# sw4.net
KiCad netlist of a schematic drawn in EAGLE
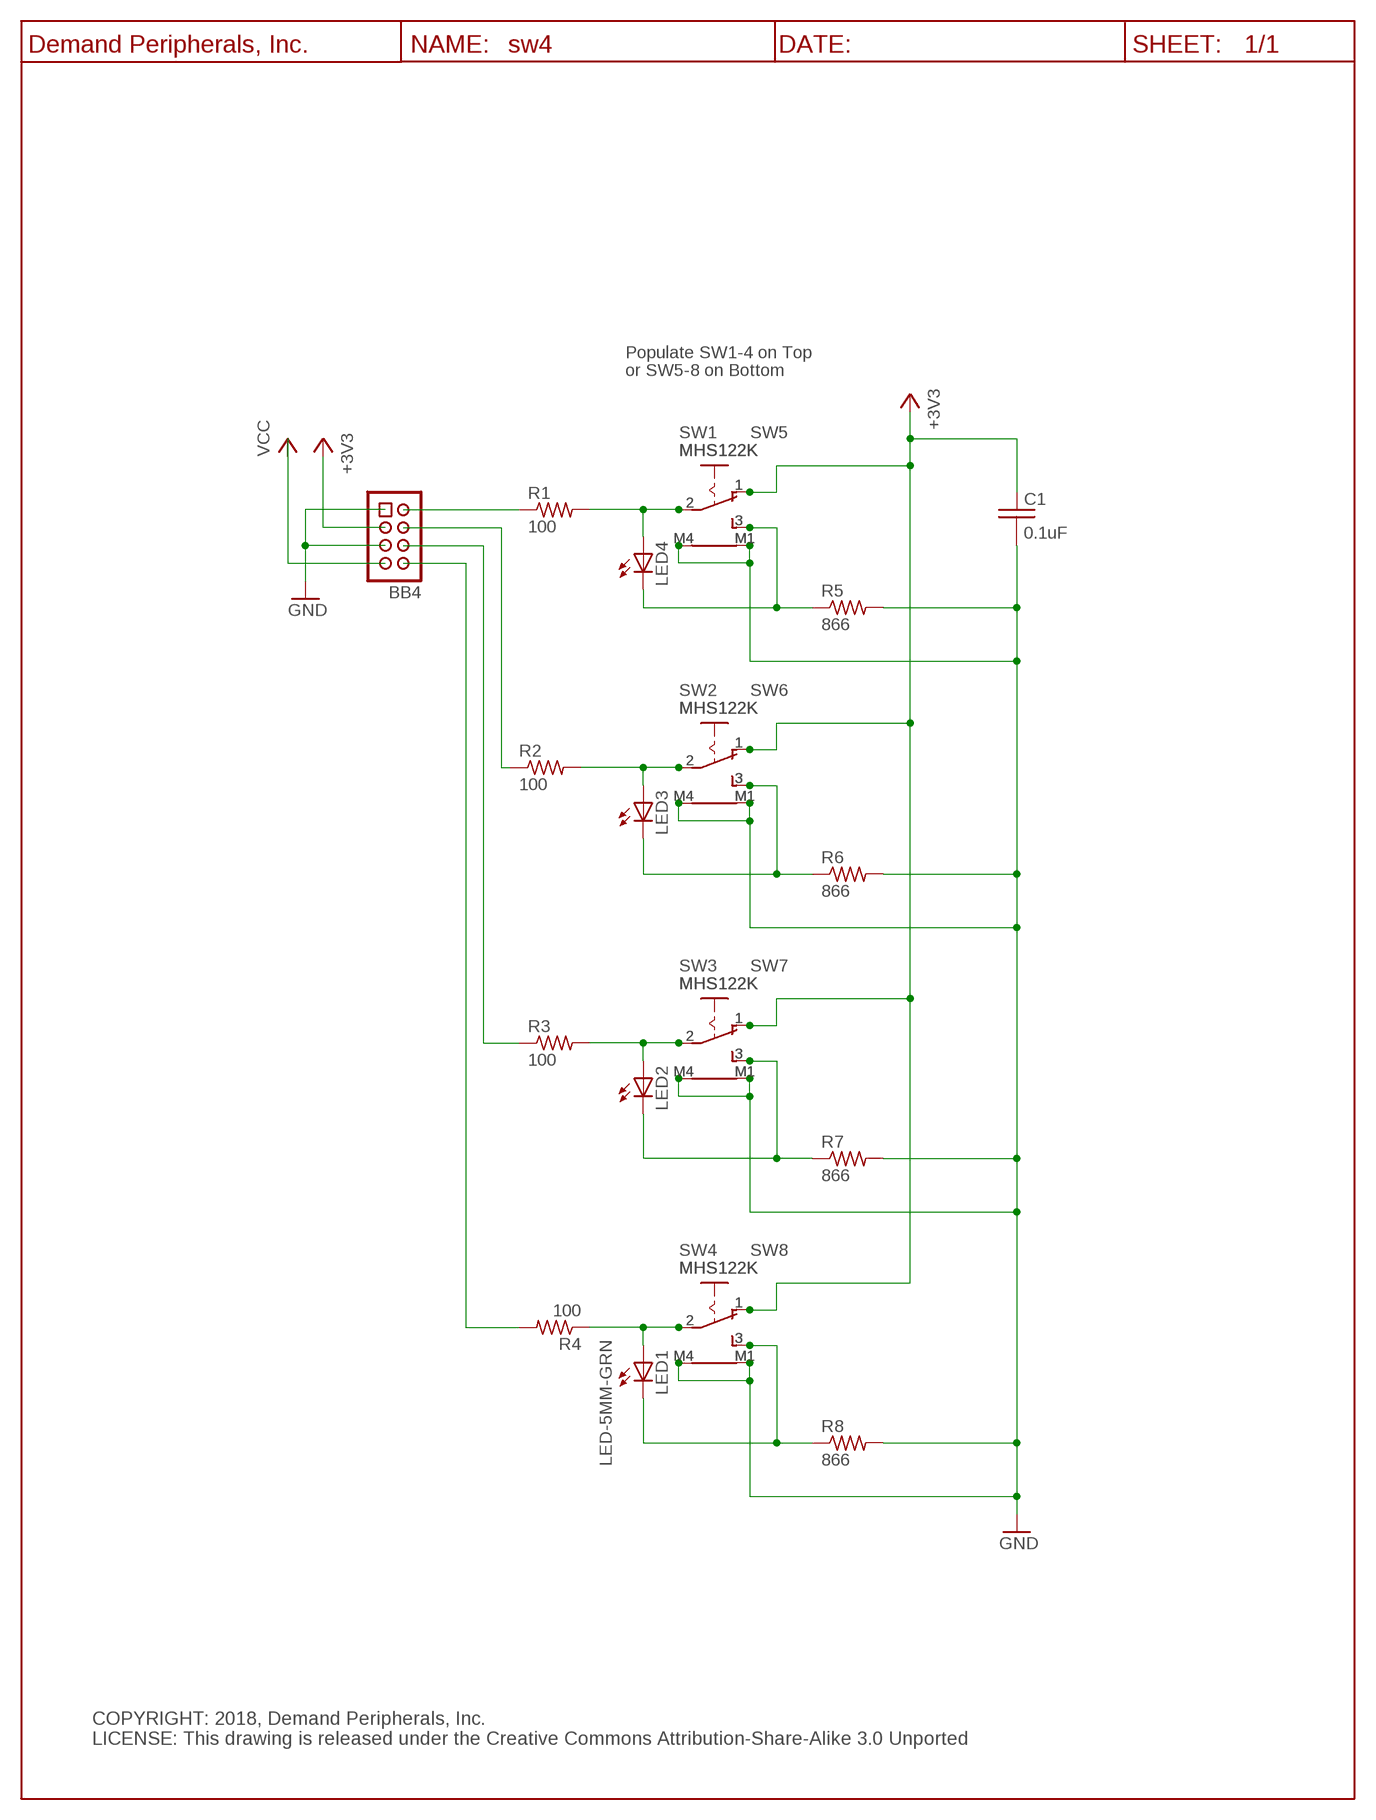
[diagram p0: schematic, sheet 1]

(export (version "E")
  (design (tool "Eeschema 10.0.6"))
  (components
    (comp (ref "BB4")
      (value "hdr4x2")
      (footprint "eagle-import:HDR-4X2")
      (libsource (lib "eagle-import") (part "HDR-4X2-SHR"))
    )
    (comp (ref "C1")
      (value "0.1uF")
      (footprint "eagle-import:C0603")
      (libsource (lib "eagle-import") (part "C0.1UF_C0603"))
    )
    (comp (ref "LED1")
      (value "LED-5MM-GRN")
      (footprint "eagle-import:LED5MM")
      (libsource (lib "eagle-import") (part "LED-5MM-GRN"))
    )
    (comp (ref "LED2")
      (value "LED-5MM-GRN")
      (footprint "eagle-import:LED5MM")
      (libsource (lib "eagle-import") (part "LED-5MM-GRN"))
    )
    (comp (ref "LED3")
      (value "LED-5MM-GRN")
      (footprint "eagle-import:LED5MM")
      (libsource (lib "eagle-import") (part "LED-5MM-GRN"))
    )
    (comp (ref "LED4")
      (value "LED-5MM-GRN")
      (footprint "eagle-import:LED5MM")
      (libsource (lib "eagle-import") (part "LED-5MM-GRN"))
    )
    (comp (ref "R1")
      (value "100")
      (footprint "eagle-import:R0603")
      (libsource (lib "eagle-import") (part "R100_R0603"))
    )
    (comp (ref "R2")
      (value "100")
      (footprint "eagle-import:R0603")
      (libsource (lib "eagle-import") (part "R100_R0603"))
    )
    (comp (ref "R3")
      (value "100")
      (footprint "eagle-import:R0603")
      (libsource (lib "eagle-import") (part "R100_R0603"))
    )
    (comp (ref "R4")
      (value "100")
      (footprint "eagle-import:R0603")
      (libsource (lib "eagle-import") (part "R100_R0603"))
    )
    (comp (ref "R5")
      (value "866")
      (footprint "eagle-import:R0603")
      (libsource (lib "eagle-import") (part "R866_R0603"))
    )
    (comp (ref "R6")
      (value "866")
      (footprint "eagle-import:R0603")
      (libsource (lib "eagle-import") (part "R866_R0603"))
    )
    (comp (ref "R7")
      (value "866")
      (footprint "eagle-import:R0603")
      (libsource (lib "eagle-import") (part "R866_R0603"))
    )
    (comp (ref "R8")
      (value "866")
      (footprint "eagle-import:R0603")
      (libsource (lib "eagle-import") (part "R866_R0603"))
    )
    (comp (ref "SW1")
      (value "MHS122K")
      (footprint "eagle-import:MHS122K")
      (libsource (lib "eagle-import") (part "MHS122K"))
    )
    (comp (ref "SW2")
      (value "MHS122K")
      (footprint "eagle-import:MHS122K")
      (libsource (lib "eagle-import") (part "MHS122K"))
    )
    (comp (ref "SW3")
      (value "MHS122K")
      (footprint "eagle-import:MHS122K")
      (libsource (lib "eagle-import") (part "MHS122K"))
    )
    (comp (ref "SW4")
      (value "MHS122K")
      (footprint "eagle-import:MHS122K")
      (libsource (lib "eagle-import") (part "MHS122K"))
    )
    (comp (ref "SW5")
      (value "MHS122K")
      (footprint "eagle-import:MHS122K")
      (libsource (lib "eagle-import") (part "MHS122K"))
    )
    (comp (ref "SW6")
      (value "MHS122K")
      (footprint "eagle-import:MHS122K")
      (libsource (lib "eagle-import") (part "MHS122K"))
    )
    (comp (ref "SW7")
      (value "MHS122K")
      (footprint "eagle-import:MHS122K")
      (libsource (lib "eagle-import") (part "MHS122K"))
    )
    (comp (ref "SW8")
      (value "MHS122K")
      (footprint "eagle-import:MHS122K")
      (libsource (lib "eagle-import") (part "MHS122K"))
    )
    (comp (ref "U$1")
      (value "DP_FRAME_P")
      (footprint "eagle-import:P_FRAME")
      (libsource (lib "eagle-import") (part "DP_FRAME_P"))
    )
  )
  (nets
    (net (code "1") (name "+3V3") (class "Default")
      (node (ref "BB4") (pin "3") (pinfunction "3_3") (pintype "passive"))
      (node (ref "C1") (pin "1") (pinfunction "1_1") (pintype "passive"))
      (node (ref "SW1") (pin "1") (pinfunction "O_1") (pintype "passive"))
      (node (ref "SW2") (pin "1") (pinfunction "O_1") (pintype "passive"))
      (node (ref "SW3") (pin "1") (pinfunction "O_1") (pintype "passive"))
      (node (ref "SW4") (pin "1") (pinfunction "O_1") (pintype "passive"))
      (node (ref "SW5") (pin "1") (pinfunction "O_1") (pintype "passive"))
      (node (ref "SW6") (pin "1") (pinfunction "O_1") (pintype "passive"))
      (node (ref "SW7") (pin "1") (pinfunction "O_1") (pintype "passive"))
      (node (ref "SW8") (pin "1") (pinfunction "O_1") (pintype "passive"))
    )
    (net (code "2") (name "GND") (class "Default")
      (node (ref "BB4") (pin "1") (pinfunction "1_1") (pintype "passive"))
      (node (ref "BB4") (pin "5") (pinfunction "5_5") (pintype "passive"))
      (node (ref "C1") (pin "2") (pinfunction "2_2") (pintype "passive"))
      (node (ref "R5") (pin "2") (pinfunction "2_2") (pintype "passive"))
      (node (ref "R6") (pin "2") (pinfunction "2_2") (pintype "passive"))
      (node (ref "R7") (pin "2") (pinfunction "2_2") (pintype "passive"))
      (node (ref "R8") (pin "2") (pinfunction "2_2") (pintype "passive"))
      (node (ref "SW1") (pin "M1") (pinfunction "B1_M1") (pintype "passive"))
      (node (ref "SW1") (pin "M4") (pinfunction "B_M4") (pintype "passive"))
      (node (ref "SW2") (pin "M1") (pinfunction "B1_M1") (pintype "passive"))
      (node (ref "SW2") (pin "M4") (pinfunction "B_M4") (pintype "passive"))
      (node (ref "SW3") (pin "M1") (pinfunction "B1_M1") (pintype "passive"))
      (node (ref "SW3") (pin "M4") (pinfunction "B_M4") (pintype "passive"))
      (node (ref "SW4") (pin "M1") (pinfunction "B1_M1") (pintype "passive"))
      (node (ref "SW4") (pin "M4") (pinfunction "B_M4") (pintype "passive"))
      (node (ref "SW5") (pin "M1") (pinfunction "B1_M1") (pintype "passive"))
      (node (ref "SW5") (pin "M4") (pinfunction "B_M4") (pintype "passive"))
      (node (ref "SW6") (pin "M1") (pinfunction "B1_M1") (pintype "passive"))
      (node (ref "SW6") (pin "M4") (pinfunction "B_M4") (pintype "passive"))
      (node (ref "SW7") (pin "M1") (pinfunction "B1_M1") (pintype "passive"))
      (node (ref "SW7") (pin "M4") (pinfunction "B_M4") (pintype "passive"))
      (node (ref "SW8") (pin "M1") (pinfunction "B1_M1") (pintype "passive"))
      (node (ref "SW8") (pin "M4") (pinfunction "B_M4") (pintype "passive"))
    )
    (net (code "3") (name "Net-(BB4-Pad2)") (class "Default")
      (node (ref "BB4") (pin "2") (pinfunction "2_2") (pintype "passive"))
      (node (ref "R1") (pin "1") (pinfunction "1_1") (pintype "passive"))
    )
    (net (code "4") (name "Net-(BB4-Pad4)") (class "Default")
      (node (ref "BB4") (pin "4") (pinfunction "4_4") (pintype "passive"))
      (node (ref "R2") (pin "1") (pinfunction "1_1") (pintype "passive"))
    )
    (net (code "5") (name "Net-(BB4-Pad6)") (class "Default")
      (node (ref "BB4") (pin "6") (pinfunction "6_6") (pintype "passive"))
      (node (ref "R3") (pin "1") (pinfunction "1_1") (pintype "passive"))
    )
    (net (code "6") (name "Net-(BB4-Pad8)") (class "Default")
      (node (ref "BB4") (pin "8") (pinfunction "8_8") (pintype "passive"))
      (node (ref "R4") (pin "2") (pinfunction "2_2") (pintype "passive"))
    )
    (net (code "7") (name "Net-(SW1-P)") (class "Default")
      (node (ref "LED4") (pin "A") (pinfunction "A_A") (pintype "passive"))
      (node (ref "R1") (pin "2") (pinfunction "2_2") (pintype "passive"))
      (node (ref "SW1") (pin "2") (pinfunction "P_2") (pintype "passive"))
      (node (ref "SW5") (pin "2") (pinfunction "P_2") (pintype "passive"))
    )
    (net (code "8") (name "Net-(SW1-S)") (class "Default")
      (node (ref "LED4") (pin "C") (pinfunction "C_C") (pintype "passive"))
      (node (ref "R5") (pin "1") (pinfunction "1_1") (pintype "passive"))
      (node (ref "SW1") (pin "3") (pinfunction "S_3") (pintype "passive"))
      (node (ref "SW5") (pin "3") (pinfunction "S_3") (pintype "passive"))
    )
    (net (code "9") (name "Net-(SW2-P)") (class "Default")
      (node (ref "LED3") (pin "A") (pinfunction "A_A") (pintype "passive"))
      (node (ref "R2") (pin "2") (pinfunction "2_2") (pintype "passive"))
      (node (ref "SW2") (pin "2") (pinfunction "P_2") (pintype "passive"))
      (node (ref "SW6") (pin "2") (pinfunction "P_2") (pintype "passive"))
    )
    (net (code "10") (name "Net-(SW2-S)") (class "Default")
      (node (ref "LED3") (pin "C") (pinfunction "C_C") (pintype "passive"))
      (node (ref "R6") (pin "1") (pinfunction "1_1") (pintype "passive"))
      (node (ref "SW2") (pin "3") (pinfunction "S_3") (pintype "passive"))
      (node (ref "SW6") (pin "3") (pinfunction "S_3") (pintype "passive"))
    )
    (net (code "11") (name "Net-(SW3-P)") (class "Default")
      (node (ref "LED2") (pin "A") (pinfunction "A_A") (pintype "passive"))
      (node (ref "R3") (pin "2") (pinfunction "2_2") (pintype "passive"))
      (node (ref "SW3") (pin "2") (pinfunction "P_2") (pintype "passive"))
      (node (ref "SW7") (pin "2") (pinfunction "P_2") (pintype "passive"))
    )
    (net (code "12") (name "Net-(SW3-S)") (class "Default")
      (node (ref "LED2") (pin "C") (pinfunction "C_C") (pintype "passive"))
      (node (ref "R7") (pin "1") (pinfunction "1_1") (pintype "passive"))
      (node (ref "SW3") (pin "3") (pinfunction "S_3") (pintype "passive"))
      (node (ref "SW7") (pin "3") (pinfunction "S_3") (pintype "passive"))
    )
    (net (code "13") (name "Net-(SW4-P)") (class "Default")
      (node (ref "LED1") (pin "A") (pinfunction "A_A") (pintype "passive"))
      (node (ref "R4") (pin "1") (pinfunction "1_1") (pintype "passive"))
      (node (ref "SW4") (pin "2") (pinfunction "P_2") (pintype "passive"))
      (node (ref "SW8") (pin "2") (pinfunction "P_2") (pintype "passive"))
    )
    (net (code "14") (name "Net-(SW4-S)") (class "Default")
      (node (ref "LED1") (pin "C") (pinfunction "C_C") (pintype "passive"))
      (node (ref "R8") (pin "1") (pinfunction "1_1") (pintype "passive"))
      (node (ref "SW4") (pin "3") (pinfunction "S_3") (pintype "passive"))
      (node (ref "SW8") (pin "3") (pinfunction "S_3") (pintype "passive"))
    )
    (net (code "15") (name "VCC") (class "Default")
      (node (ref "BB4") (pin "7") (pinfunction "7_7") (pintype "passive"))
    )
  )
)
